# Grove_-_I2C_Motor_Driver.net
KiCad netlist of a schematic drawn in EAGLE
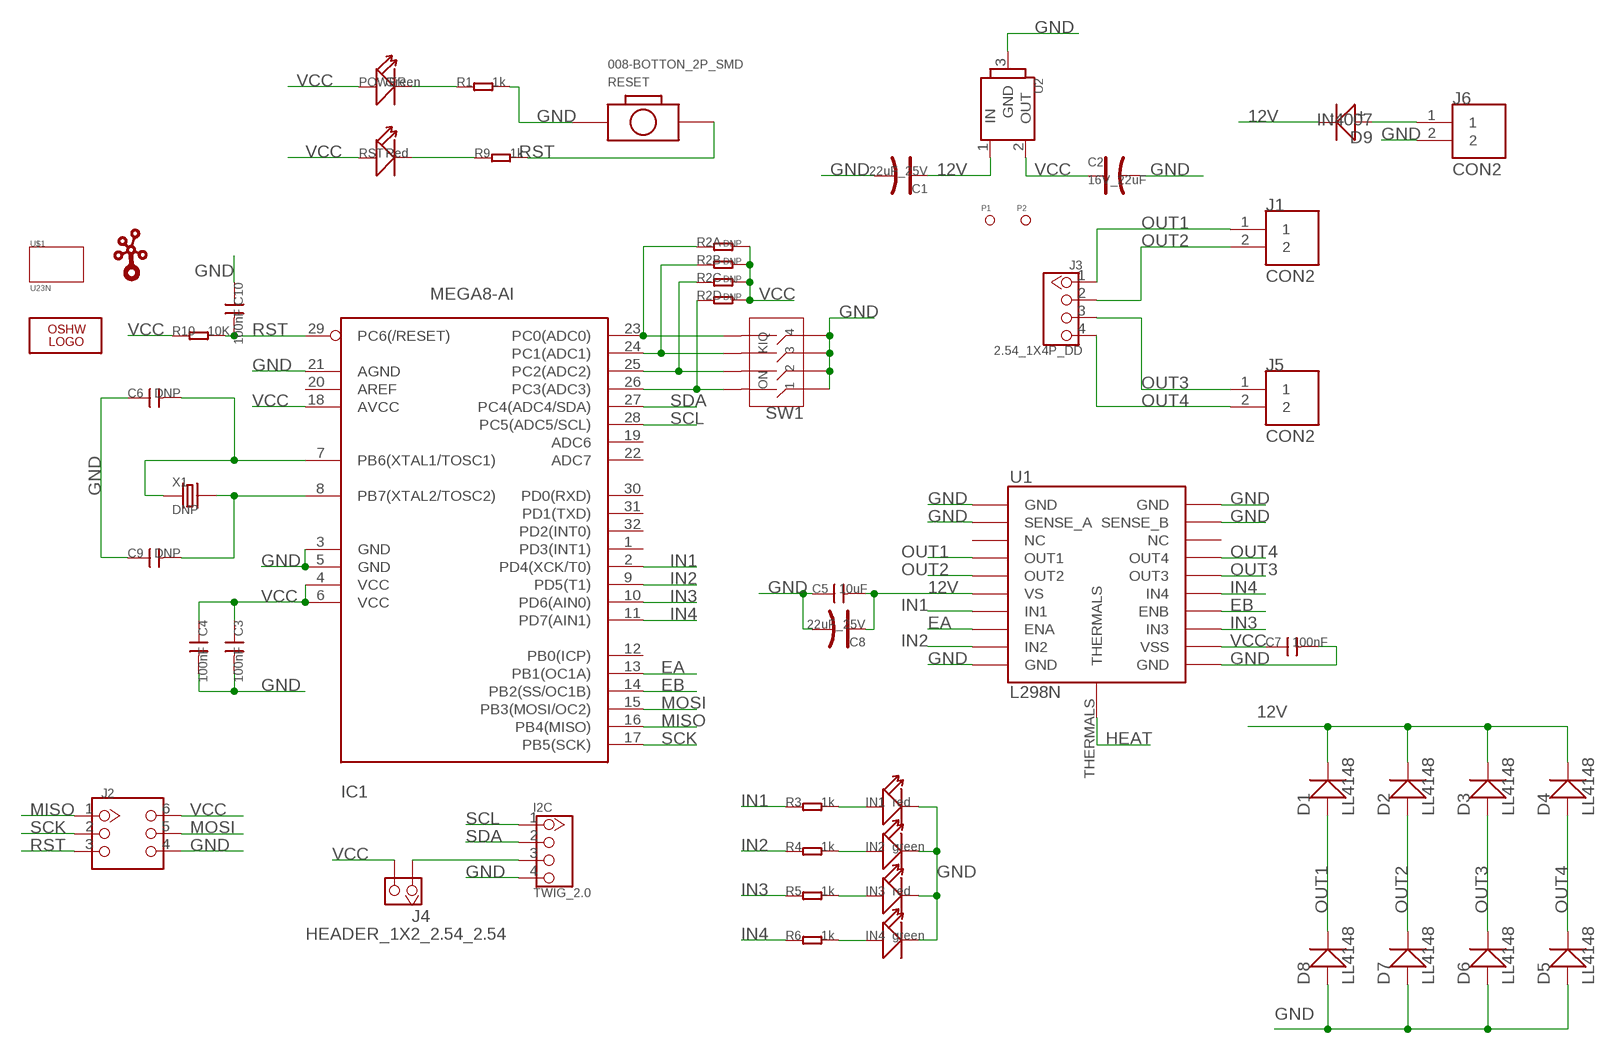
[diagram p0: schematic, sheet 1]

(export (version "E")
  (design (tool "Eeschema 10.0.6"))
  (components
    (comp (ref "C1")
      (value "22uF_25V")
      (footprint "eagle-import:AVX-C")
      (libsource (lib "eagle-import") (part "CAP-AVX-C"))
    )
    (comp (ref "C2")
      (value "16V_22uF")
      (footprint "eagle-import:AVX-B")
      (libsource (lib "eagle-import") (part "CAP-AVX-B"))
    )
    (comp (ref "C3")
      (value "100nF")
      (footprint "eagle-import:0603")
      (libsource (lib "eagle-import") (part "C-0603"))
    )
    (comp (ref "C4")
      (value "100nF")
      (footprint "eagle-import:0603")
      (libsource (lib "eagle-import") (part "C-0603"))
    )
    (comp (ref "C5")
      (value "10uF")
      (footprint "eagle-import:0805")
      (libsource (lib "eagle-import") (part "C-0805"))
    )
    (comp (ref "C6")
      (value "DNP")
      (footprint "eagle-import:0603_S")
      (libsource (lib "eagle-import") (part "006-C3035"))
    )
    (comp (ref "C7")
      (value "100nF")
      (footprint "eagle-import:0603")
      (libsource (lib "eagle-import") (part "C-0603"))
    )
    (comp (ref "C8")
      (value "22uF_25V")
      (footprint "eagle-import:AVX-C")
      (libsource (lib "eagle-import") (part "CAP-AVX-C"))
    )
    (comp (ref "C9")
      (value "DNP")
      (footprint "eagle-import:0603_S")
      (libsource (lib "eagle-import") (part "006-C3035"))
    )
    (comp (ref "C10")
      (value "100nF")
      (footprint "eagle-import:0603_S")
      (libsource (lib "eagle-import") (part "006-C3035"))
    )
    (comp (ref "D1")
      (value "LL4148")
      (footprint "eagle-import:SOD123")
      (libsource (lib "eagle-import") (part "D'1206'"))
    )
    (comp (ref "D2")
      (value "LL4148")
      (footprint "eagle-import:SOD123")
      (libsource (lib "eagle-import") (part "D'1206'"))
    )
    (comp (ref "D3")
      (value "LL4148")
      (footprint "eagle-import:SOD123")
      (libsource (lib "eagle-import") (part "D'1206'"))
    )
    (comp (ref "D4")
      (value "LL4148")
      (footprint "eagle-import:SOD123")
      (libsource (lib "eagle-import") (part "D'1206'"))
    )
    (comp (ref "D5")
      (value "LL4148")
      (footprint "eagle-import:SOD123")
      (libsource (lib "eagle-import") (part "D'1206'"))
    )
    (comp (ref "D6")
      (value "LL4148")
      (footprint "eagle-import:SOD123")
      (libsource (lib "eagle-import") (part "D'1206'"))
    )
    (comp (ref "D7")
      (value "LL4148")
      (footprint "eagle-import:SOD123")
      (libsource (lib "eagle-import") (part "D'1206'"))
    )
    (comp (ref "D8")
      (value "LL4148")
      (footprint "eagle-import:SOD123")
      (libsource (lib "eagle-import") (part "D'1206'"))
    )
    (comp (ref "D9")
      (value "IN4007")
      (footprint "eagle-import:D2010@1")
      (libsource (lib "eagle-import") (part "010-D2010"))
    )
    (comp (ref "I2C")
      (value "TWIG_2.0")
      (footprint "eagle-import:2.0_1X4")
      (libsource (lib "eagle-import") (part "TWIG_2.0"))
    )
    (comp (ref "IC1")
      (value "MEGA8-AI")
      (footprint "eagle-import:TQFP32-08")
      (libsource (lib "eagle-import") (part "MEGA8-AI"))
    )
    (comp (ref "IN1")
      (value "red")
      (footprint "eagle-import:D0603")
      (libsource (lib "eagle-import") (part "007-LED0603"))
    )
    (comp (ref "IN2")
      (value "green")
      (footprint "eagle-import:D0603")
      (libsource (lib "eagle-import") (part "007-LED0603"))
    )
    (comp (ref "IN3")
      (value "red")
      (footprint "eagle-import:D0603")
      (libsource (lib "eagle-import") (part "007-LED0603"))
    )
    (comp (ref "IN4")
      (value "green")
      (footprint "eagle-import:D0603")
      (libsource (lib "eagle-import") (part "007-LED0603"))
    )
    (comp (ref "J1")
      (value "CON2")
      (footprint "eagle-import:CON2")
      (libsource (lib "eagle-import") (part "CON2"))
    )
    (comp (ref "J2")
      (value "HEADER-2X3P-60/35MIL")
      (footprint "eagle-import:2X3P-2.54-65_35MIL")
      (libsource (lib "eagle-import") (part "HEADER-2X3P-60/35MIL"))
    )
    (comp (ref "J3")
      (value "2.54_1X4P_DD")
      (footprint "eagle-import:CK_1X4")
      (libsource (lib "eagle-import") (part "2.54_1X4P_DD"))
    )
    (comp (ref "J4")
      (value "HEADER_1X2_2.54_2.54")
      (footprint "eagle-import:65_35")
      (libsource (lib "eagle-import") (part "HEADER_1X2_2.54_2.54"))
    )
    (comp (ref "J5")
      (value "CON2")
      (footprint "eagle-import:CON2")
      (libsource (lib "eagle-import") (part "CON2"))
    )
    (comp (ref "J6")
      (value "CON2")
      (footprint "eagle-import:CON2")
      (libsource (lib "eagle-import") (part "CON2"))
    )
    (comp (ref "LOGO2")
      (value "LOGO-OSHW-FILLX0200-NT")
      (footprint "eagle-import:OSHW_FILLX200_NOTEXT")
      (libsource (lib "eagle-import") (part "LOGO-OSHW-FILLX0200-NT"))
    )
    (comp (ref "P1")
      (value "PAD-MARK")
      (footprint "eagle-import:ROUND-MARK-1.0")
      (fields (field (name "PARTNO") "DNP"))
      (libsource (lib "eagle-import") (part "PAD-MARK"))
    )
    (comp (ref "P2")
      (value "PAD-MARK")
      (footprint "eagle-import:ROUND-MARK-1.0")
      (fields (field (name "PARTNO") "DNP"))
      (libsource (lib "eagle-import") (part "PAD-MARK"))
    )
    (comp (ref "POWER")
      (value "Green")
      (footprint "eagle-import:D0603")
      (libsource (lib "eagle-import") (part "007-LED0603"))
    )
    (comp (ref "R1")
      (value "1k")
      (footprint "eagle-import:0603-1")
      (libsource (lib "eagle-import") (part "005-R0603"))
    )
    (comp (ref "R2")
      (value "DNP")
      (footprint "eagle-import:1206-8-3.3X2.4")
      (libsource (lib "eagle-import") (part "R-4R-1206"))
    )
    (comp (ref "R3")
      (value "1k")
      (footprint "eagle-import:0603-1")
      (libsource (lib "eagle-import") (part "005-R0603"))
    )
    (comp (ref "R4")
      (value "1k")
      (footprint "eagle-import:0603-1")
      (libsource (lib "eagle-import") (part "005-R0603"))
    )
    (comp (ref "R5")
      (value "1k")
      (footprint "eagle-import:0603-1")
      (libsource (lib "eagle-import") (part "005-R0603"))
    )
    (comp (ref "R6")
      (value "1k")
      (footprint "eagle-import:0603-1")
      (libsource (lib "eagle-import") (part "005-R0603"))
    )
    (comp (ref "R9")
      (value "1k")
      (footprint "eagle-import:0603-1")
      (libsource (lib "eagle-import") (part "005-R0603"))
    )
    (comp (ref "R10")
      (value "10K")
      (footprint "eagle-import:0603-1")
      (libsource (lib "eagle-import") (part "005-R0603"))
    )
    (comp (ref "RESET")
      (value "008-BOTTON_2P_SMD")
      (footprint "eagle-import:BOTTON_1")
      (libsource (lib "eagle-import") (part "008-BOTTON_2P_SMD"))
    )
    (comp (ref "RST")
      (value "Red")
      (footprint "eagle-import:D0603")
      (libsource (lib "eagle-import") (part "007-LED0603"))
    )
    (comp (ref "SW1")
      (value "SWITCH-KM-04'KM-04'")
      (footprint "eagle-import:8P-SMD-11.8X6.8X3.3H")
      (libsource (lib "eagle-import") (part "SWITCH-KM-04'KM-04'"))
    )
    (comp (ref "U$1")
      (value "U23N")
      (footprint "eagle-import:U2_3N")
      (libsource (lib "eagle-import") (part "U23N"))
    )
    (comp (ref "U$3")
      (value "TWIGLOGOTWIGLOGO_SMALL")
      (footprint "eagle-import:TWIGLOGO_SMALL")
      (libsource (lib "eagle-import") (part "TWIGLOGOTWIGLOGO_SMALL"))
    )
    (comp (ref "U1")
      (value "L298N")
      (footprint "eagle-import:POWERSO20")
      (libsource (lib "eagle-import") (part "L298_BRIDGE_DRIVER"))
    )
    (comp (ref "U2")
      (value "78M05-TO252")
      (footprint "eagle-import:TO252")
      (libsource (lib "eagle-import") (part "78M05-TO252"))
    )
    (comp (ref "X1")
      (value "DNP")
      (footprint "eagle-import:2P-SMD-5X3.2")
      (libsource (lib "eagle-import") (part "CRYSTAL-5032"))
    )
  )
  (nets
    (net (code "1") (name "/12V") (class "Default")
      (node (ref "C1") (pin "+") (pinfunction "+_+") (pintype "passive"))
      (node (ref "C5") (pin "2") (pinfunction "2_2") (pintype "passive"))
      (node (ref "C8") (pin "+") (pinfunction "+_+") (pintype "passive"))
      (node (ref "D1") (pin "-") (pinfunction "-_-") (pintype "passive"))
      (node (ref "D2") (pin "-") (pinfunction "-_-") (pintype "passive"))
      (node (ref "D3") (pin "-") (pinfunction "-_-") (pintype "passive"))
      (node (ref "D4") (pin "-") (pinfunction "-_-") (pintype "passive"))
      (node (ref "D9") (pin "-") (pinfunction "-_-") (pintype "passive"))
      (node (ref "U1") (pin "P$6") (pinfunction "VS_P$6") (pintype "bidirectional"))
      (node (ref "U2") (pin "1") (pinfunction "IN_1") (pintype "bidirectional"))
    )
    (net (code "2") (name "/EA") (class "Default")
      (node (ref "IC1") (pin "13") (pinfunction "PB1(OC1A)_13") (pintype "bidirectional"))
      (node (ref "U1") (pin "P$8") (pinfunction "ENA_P$8") (pintype "bidirectional"))
    )
    (net (code "3") (name "/EB") (class "Default")
      (node (ref "IC1") (pin "14") (pinfunction "PB2(SS/OC1B)_14") (pintype "bidirectional"))
      (node (ref "U1") (pin "P$14") (pinfunction "ENB_P$14") (pintype "bidirectional"))
    )
    (net (code "4") (name "/GND") (class "Default")
      (node (ref "C1") (pin "-") (pinfunction "-_-") (pintype "passive"))
      (node (ref "C10") (pin "1") (pinfunction "1_1") (pintype "passive"))
      (node (ref "C2") (pin "-") (pinfunction "-_-") (pintype "passive"))
      (node (ref "C3") (pin "2") (pinfunction "2_2") (pintype "passive"))
      (node (ref "C4") (pin "2") (pinfunction "2_2") (pintype "passive"))
      (node (ref "C5") (pin "1") (pinfunction "1_1") (pintype "passive"))
      (node (ref "C6") (pin "1") (pinfunction "1_1") (pintype "passive"))
      (node (ref "C7") (pin "2") (pinfunction "2_2") (pintype "passive"))
      (node (ref "C8") (pin "-") (pinfunction "-_-") (pintype "passive"))
      (node (ref "C9") (pin "1") (pinfunction "1_1") (pintype "passive"))
      (node (ref "D5") (pin "+") (pinfunction "+_+") (pintype "passive"))
      (node (ref "D6") (pin "+") (pinfunction "+_+") (pintype "passive"))
      (node (ref "D7") (pin "+") (pinfunction "+_+") (pintype "passive"))
      (node (ref "D8") (pin "+") (pinfunction "+_+") (pintype "passive"))
      (node (ref "I2C") (pin "4") (pinfunction "4_4") (pintype "bidirectional"))
      (node (ref "IC1") (pin "21") (pinfunction "AGND_21") (pintype "bidirectional"))
      (node (ref "IC1") (pin "3") (pinfunction "GND_3") (pintype "bidirectional"))
      (node (ref "IC1") (pin "5") (pinfunction "GND_5") (pintype "bidirectional"))
      (node (ref "IN1") (pin "-") (pinfunction "-_-") (pintype "passive"))
      (node (ref "IN2") (pin "-") (pinfunction "-_-") (pintype "passive"))
      (node (ref "IN3") (pin "-") (pinfunction "-_-") (pintype "passive"))
      (node (ref "IN4") (pin "-") (pinfunction "-_-") (pintype "passive"))
      (node (ref "J2") (pin "4") (pinfunction "4_4") (pintype "bidirectional"))
      (node (ref "J6") (pin "2") (pinfunction "2_2") (pintype "bidirectional"))
      (node (ref "R1") (pin "2") (pinfunction "2_2") (pintype "passive"))
      (node (ref "RESET") (pin "1") (pinfunction "1_1") (pintype "bidirectional"))
      (node (ref "SW1") (pin "1") (pinfunction "1_1") (pintype "bidirectional"))
      (node (ref "SW1") (pin "2") (pinfunction "2_2") (pintype "bidirectional"))
      (node (ref "SW1") (pin "3") (pinfunction "3_3") (pintype "bidirectional"))
      (node (ref "SW1") (pin "4") (pinfunction "4_4") (pintype "bidirectional"))
      (node (ref "U1") (pin "P$1") (pinfunction "GND_P$1") (pintype "bidirectional"))
      (node (ref "U1") (pin "P$10") (pinfunction "GND_P$10") (pintype "bidirectional"))
      (node (ref "U1") (pin "P$11") (pinfunction "GND_P$11") (pintype "bidirectional"))
      (node (ref "U1") (pin "P$19") (pinfunction "SENSE_B_P$19") (pintype "bidirectional"))
      (node (ref "U1") (pin "P$2") (pinfunction "SENSE_A_P$2") (pintype "bidirectional"))
      (node (ref "U1") (pin "P$20") (pinfunction "GND_P$20") (pintype "bidirectional"))
      (node (ref "U2") (pin "3") (pinfunction "GND_3") (pintype "bidirectional"))
    )
    (net (code "5") (name "/HEAT") (class "Default")
      (node (ref "U1") (pin "THERMALS") (pinfunction "THERMALS_THERMALS") (pintype "bidirectional"))
    )
    (net (code "6") (name "/IN1") (class "Default")
      (node (ref "IC1") (pin "2") (pinfunction "PD4(XCK/T0)_2") (pintype "bidirectional"))
      (node (ref "R3") (pin "1") (pinfunction "1_1") (pintype "passive"))
      (node (ref "U1") (pin "P$7") (pinfunction "IN1_P$7") (pintype "bidirectional"))
    )
    (net (code "7") (name "/IN2") (class "Default")
      (node (ref "IC1") (pin "9") (pinfunction "PD5(T1)_9") (pintype "bidirectional"))
      (node (ref "R4") (pin "1") (pinfunction "1_1") (pintype "passive"))
      (node (ref "U1") (pin "P$9") (pinfunction "IN2_P$9") (pintype "bidirectional"))
    )
    (net (code "8") (name "/IN3") (class "Default")
      (node (ref "IC1") (pin "10") (pinfunction "PD6(AIN0)_10") (pintype "bidirectional"))
      (node (ref "R5") (pin "1") (pinfunction "1_1") (pintype "passive"))
      (node (ref "U1") (pin "P$13") (pinfunction "IN3_P$13") (pintype "bidirectional"))
    )
    (net (code "9") (name "/IN4") (class "Default")
      (node (ref "IC1") (pin "11") (pinfunction "PD7(AIN1)_11") (pintype "bidirectional"))
      (node (ref "R6") (pin "1") (pinfunction "1_1") (pintype "passive"))
      (node (ref "U1") (pin "P$15") (pinfunction "IN4_P$15") (pintype "bidirectional"))
    )
    (net (code "10") (name "/MISO") (class "Default")
      (node (ref "IC1") (pin "16") (pinfunction "PB4(MISO)_16") (pintype "bidirectional"))
      (node (ref "J2") (pin "1") (pinfunction "1_1") (pintype "bidirectional"))
    )
    (net (code "11") (name "/MOSI") (class "Default")
      (node (ref "IC1") (pin "15") (pinfunction "PB3(MOSI/OC2)_15") (pintype "bidirectional"))
      (node (ref "J2") (pin "5") (pinfunction "5_5") (pintype "bidirectional"))
    )
    (net (code "12") (name "/OUT1") (class "Default")
      (node (ref "D1") (pin "+") (pinfunction "+_+") (pintype "passive"))
      (node (ref "D8") (pin "-") (pinfunction "-_-") (pintype "passive"))
      (node (ref "J1") (pin "1") (pinfunction "1_1") (pintype "bidirectional"))
      (node (ref "J3") (pin "1") (pinfunction "P$1_1") (pintype "bidirectional"))
      (node (ref "U1") (pin "P$4") (pinfunction "OUT1_P$4") (pintype "bidirectional"))
    )
    (net (code "13") (name "/OUT2") (class "Default")
      (node (ref "D2") (pin "+") (pinfunction "+_+") (pintype "passive"))
      (node (ref "D7") (pin "-") (pinfunction "-_-") (pintype "passive"))
      (node (ref "J1") (pin "2") (pinfunction "2_2") (pintype "bidirectional"))
      (node (ref "J3") (pin "2") (pinfunction "P$2_2") (pintype "bidirectional"))
      (node (ref "U1") (pin "P$5") (pinfunction "OUT2_P$5") (pintype "bidirectional"))
    )
    (net (code "14") (name "/OUT3") (class "Default")
      (node (ref "D3") (pin "+") (pinfunction "+_+") (pintype "passive"))
      (node (ref "D6") (pin "-") (pinfunction "-_-") (pintype "passive"))
      (node (ref "J3") (pin "3") (pinfunction "P$3_3") (pintype "bidirectional"))
      (node (ref "J5") (pin "1") (pinfunction "1_1") (pintype "bidirectional"))
      (node (ref "U1") (pin "P$16") (pinfunction "OUT3_P$16") (pintype "bidirectional"))
    )
    (net (code "15") (name "/OUT4") (class "Default")
      (node (ref "D4") (pin "+") (pinfunction "+_+") (pintype "passive"))
      (node (ref "D5") (pin "-") (pinfunction "-_-") (pintype "passive"))
      (node (ref "J3") (pin "4") (pinfunction "P$4_4") (pintype "bidirectional"))
      (node (ref "J5") (pin "2") (pinfunction "2_2") (pintype "bidirectional"))
      (node (ref "U1") (pin "P$17") (pinfunction "OUT4_P$17") (pintype "bidirectional"))
    )
    (net (code "16") (name "/RST") (class "Default")
      (node (ref "C10") (pin "2") (pinfunction "2_2") (pintype "passive"))
      (node (ref "IC1") (pin "29") (pinfunction "PC6(/RESET)_29") (pintype "bidirectional"))
      (node (ref "J2") (pin "3") (pinfunction "3_3") (pintype "bidirectional"))
      (node (ref "R10") (pin "2") (pinfunction "2_2") (pintype "passive"))
      (node (ref "R9") (pin "2") (pinfunction "2_2") (pintype "passive"))
      (node (ref "RESET") (pin "P$2") (pinfunction "2_P$2") (pintype "bidirectional"))
    )
    (net (code "17") (name "/SCK") (class "Default")
      (node (ref "IC1") (pin "17") (pinfunction "PB5(SCK)_17") (pintype "bidirectional"))
      (node (ref "J2") (pin "2") (pinfunction "2_2") (pintype "bidirectional"))
    )
    (net (code "18") (name "/SCL") (class "Default")
      (node (ref "I2C") (pin "1") (pinfunction "1_1") (pintype "bidirectional"))
      (node (ref "IC1") (pin "28") (pinfunction "PC5(ADC5/SCL)_28") (pintype "bidirectional"))
    )
    (net (code "19") (name "/SDA") (class "Default")
      (node (ref "I2C") (pin "2") (pinfunction "2_2") (pintype "bidirectional"))
      (node (ref "IC1") (pin "27") (pinfunction "PC4(ADC4/SDA)_27") (pintype "bidirectional"))
    )
    (net (code "20") (name "/VCC") (class "Default")
      (node (ref "C2") (pin "+") (pinfunction "+_+") (pintype "passive"))
      (node (ref "C3") (pin "1") (pinfunction "1_1") (pintype "passive"))
      (node (ref "C4") (pin "1") (pinfunction "1_1") (pintype "passive"))
      (node (ref "C7") (pin "1") (pinfunction "1_1") (pintype "passive"))
      (node (ref "IC1") (pin "18") (pinfunction "AVCC_18") (pintype "bidirectional"))
      (node (ref "IC1") (pin "4") (pinfunction "VCC_4") (pintype "bidirectional"))
      (node (ref "IC1") (pin "6") (pinfunction "VCC_6") (pintype "bidirectional"))
      (node (ref "J2") (pin "6") (pinfunction "6_6") (pintype "bidirectional"))
      (node (ref "J4") (pin "2") (pinfunction "2_2") (pintype "bidirectional"))
      (node (ref "POWER") (pin "+") (pinfunction "+_+") (pintype "passive"))
      (node (ref "R10") (pin "1") (pinfunction "1_1") (pintype "passive"))
      (node (ref "R2") (pin "5") (pinfunction "2_5") (pintype "passive"))
      (node (ref "R2") (pin "6") (pinfunction "2_6") (pintype "passive"))
      (node (ref "R2") (pin "7") (pinfunction "2_7") (pintype "passive"))
      (node (ref "R2") (pin "8") (pinfunction "2_8") (pintype "passive"))
      (node (ref "RST") (pin "+") (pinfunction "+_+") (pintype "passive"))
      (node (ref "U1") (pin "P$12") (pinfunction "VSS_P$12") (pintype "bidirectional"))
      (node (ref "U2") (pin "2") (pinfunction "OUT_2") (pintype "bidirectional"))
    )
    (net (code "21") (name "Net-(D9-Pad+)") (class "Default")
      (node (ref "D9") (pin "+") (pinfunction "+_+") (pintype "passive"))
      (node (ref "J6") (pin "1") (pinfunction "1_1") (pintype "bidirectional"))
    )
    (net (code "22") (name "Net-(I2C-Pad3)") (class "Default")
      (node (ref "I2C") (pin "3") (pinfunction "3_3") (pintype "bidirectional"))
      (node (ref "J4") (pin "1") (pinfunction "1_1") (pintype "bidirectional"))
    )
    (net (code "23") (name "Net-(IC1-PB6(XTAL1{slash}TOSC1))") (class "Default")
      (node (ref "C6") (pin "2") (pinfunction "2_2") (pintype "passive"))
      (node (ref "IC1") (pin "7") (pinfunction "PB6(XTAL1/TOSC1)_7") (pintype "bidirectional"))
      (node (ref "X1") (pin "1") (pinfunction "1_1") (pintype "passive"))
    )
    (net (code "24") (name "Net-(IC1-PB7(XTAL2{slash}TOSC2))") (class "Default")
      (node (ref "C9") (pin "2") (pinfunction "2_2") (pintype "passive"))
      (node (ref "IC1") (pin "8") (pinfunction "PB7(XTAL2/TOSC2)_8") (pintype "bidirectional"))
      (node (ref "X1") (pin "2") (pinfunction "2_2") (pintype "passive"))
    )
    (net (code "25") (name "Net-(IC1-PC0(ADC0))") (class "Default")
      (node (ref "IC1") (pin "23") (pinfunction "PC0(ADC0)_23") (pintype "bidirectional"))
      (node (ref "R2") (pin "1") (pinfunction "1_1") (pintype "passive"))
      (node (ref "SW1") (pin "5") (pinfunction "5_5") (pintype "bidirectional"))
    )
    (net (code "26") (name "Net-(IC1-PC1(ADC1))") (class "Default")
      (node (ref "IC1") (pin "24") (pinfunction "PC1(ADC1)_24") (pintype "bidirectional"))
      (node (ref "R2") (pin "2") (pinfunction "1_2") (pintype "passive"))
      (node (ref "SW1") (pin "6") (pinfunction "6_6") (pintype "bidirectional"))
    )
    (net (code "27") (name "Net-(IC1-PC2(ADC2))") (class "Default")
      (node (ref "IC1") (pin "25") (pinfunction "PC2(ADC2)_25") (pintype "bidirectional"))
      (node (ref "R2") (pin "3") (pinfunction "1_3") (pintype "passive"))
      (node (ref "SW1") (pin "7") (pinfunction "7_7") (pintype "bidirectional"))
    )
    (net (code "28") (name "Net-(IC1-PC3(ADC3))") (class "Default")
      (node (ref "IC1") (pin "26") (pinfunction "PC3(ADC3)_26") (pintype "bidirectional"))
      (node (ref "R2") (pin "4") (pinfunction "1_4") (pintype "passive"))
      (node (ref "SW1") (pin "8") (pinfunction "8_8") (pintype "bidirectional"))
    )
    (net (code "29") (name "Net-(IN1-Pad+)") (class "Default")
      (node (ref "IN1") (pin "+") (pinfunction "+_+") (pintype "passive"))
      (node (ref "R3") (pin "2") (pinfunction "2_2") (pintype "passive"))
    )
    (net (code "30") (name "Net-(IN2-Pad+)") (class "Default")
      (node (ref "IN2") (pin "+") (pinfunction "+_+") (pintype "passive"))
      (node (ref "R4") (pin "2") (pinfunction "2_2") (pintype "passive"))
    )
    (net (code "31") (name "Net-(IN3-Pad+)") (class "Default")
      (node (ref "IN3") (pin "+") (pinfunction "+_+") (pintype "passive"))
      (node (ref "R5") (pin "2") (pinfunction "2_2") (pintype "passive"))
    )
    (net (code "32") (name "Net-(IN4-Pad+)") (class "Default")
      (node (ref "IN4") (pin "+") (pinfunction "+_+") (pintype "passive"))
      (node (ref "R6") (pin "2") (pinfunction "2_2") (pintype "passive"))
    )
    (net (code "33") (name "Net-(POWER-Pad-)") (class "Default")
      (node (ref "POWER") (pin "-") (pinfunction "-_-") (pintype "passive"))
      (node (ref "R1") (pin "1") (pinfunction "1_1") (pintype "passive"))
    )
    (net (code "34") (name "Net-(R9-Pad1)") (class "Default")
      (node (ref "R9") (pin "1") (pinfunction "1_1") (pintype "passive"))
      (node (ref "RST") (pin "-") (pinfunction "-_-") (pintype "passive"))
    )
    (net (code "35") (name "unconnected-(IC1-ADC6-Pad19)") (class "Default")
      (node (ref "IC1") (pin "19") (pinfunction "ADC6_19") (pintype "bidirectional"))
    )
    (net (code "36") (name "unconnected-(IC1-ADC7-Pad22)") (class "Default")
      (node (ref "IC1") (pin "22") (pinfunction "ADC7_22") (pintype "bidirectional"))
    )
    (net (code "37") (name "unconnected-(IC1-AREF-Pad20)") (class "Default")
      (node (ref "IC1") (pin "20") (pinfunction "AREF_20") (pintype "bidirectional"))
    )
    (net (code "38") (name "unconnected-(IC1-PB0(ICP)-Pad12)") (class "Default")
      (node (ref "IC1") (pin "12") (pinfunction "PB0(ICP)_12") (pintype "bidirectional"))
    )
    (net (code "39") (name "unconnected-(IC1-PD0(RXD)-Pad30)") (class "Default")
      (node (ref "IC1") (pin "30") (pinfunction "PD0(RXD)_30") (pintype "bidirectional"))
    )
    (net (code "40") (name "unconnected-(IC1-PD1(TXD)-Pad31)") (class "Default")
      (node (ref "IC1") (pin "31") (pinfunction "PD1(TXD)_31") (pintype "bidirectional"))
    )
    (net (code "41") (name "unconnected-(IC1-PD2(INT0)-Pad32)") (class "Default")
      (node (ref "IC1") (pin "32") (pinfunction "PD2(INT0)_32") (pintype "bidirectional"))
    )
    (net (code "42") (name "unconnected-(IC1-PD3(INT1)-Pad1)") (class "Default")
      (node (ref "IC1") (pin "1") (pinfunction "PD3(INT1)_1") (pintype "bidirectional"))
    )
    (net (code "43") (name "unconnected-(U1-NC-PadP$3)") (class "Default")
      (node (ref "U1") (pin "P$3") (pinfunction "NC_P$3") (pintype "bidirectional"))
    )
    (net (code "44") (name "unconnected-(U1-NC-PadP$18)") (class "Default")
      (node (ref "U1") (pin "P$18") (pinfunction "NC_P$18") (pintype "bidirectional"))
    )
  )
)
